# cyclone4.net
KiCad netlist of a schematic drawn in Altium Designer
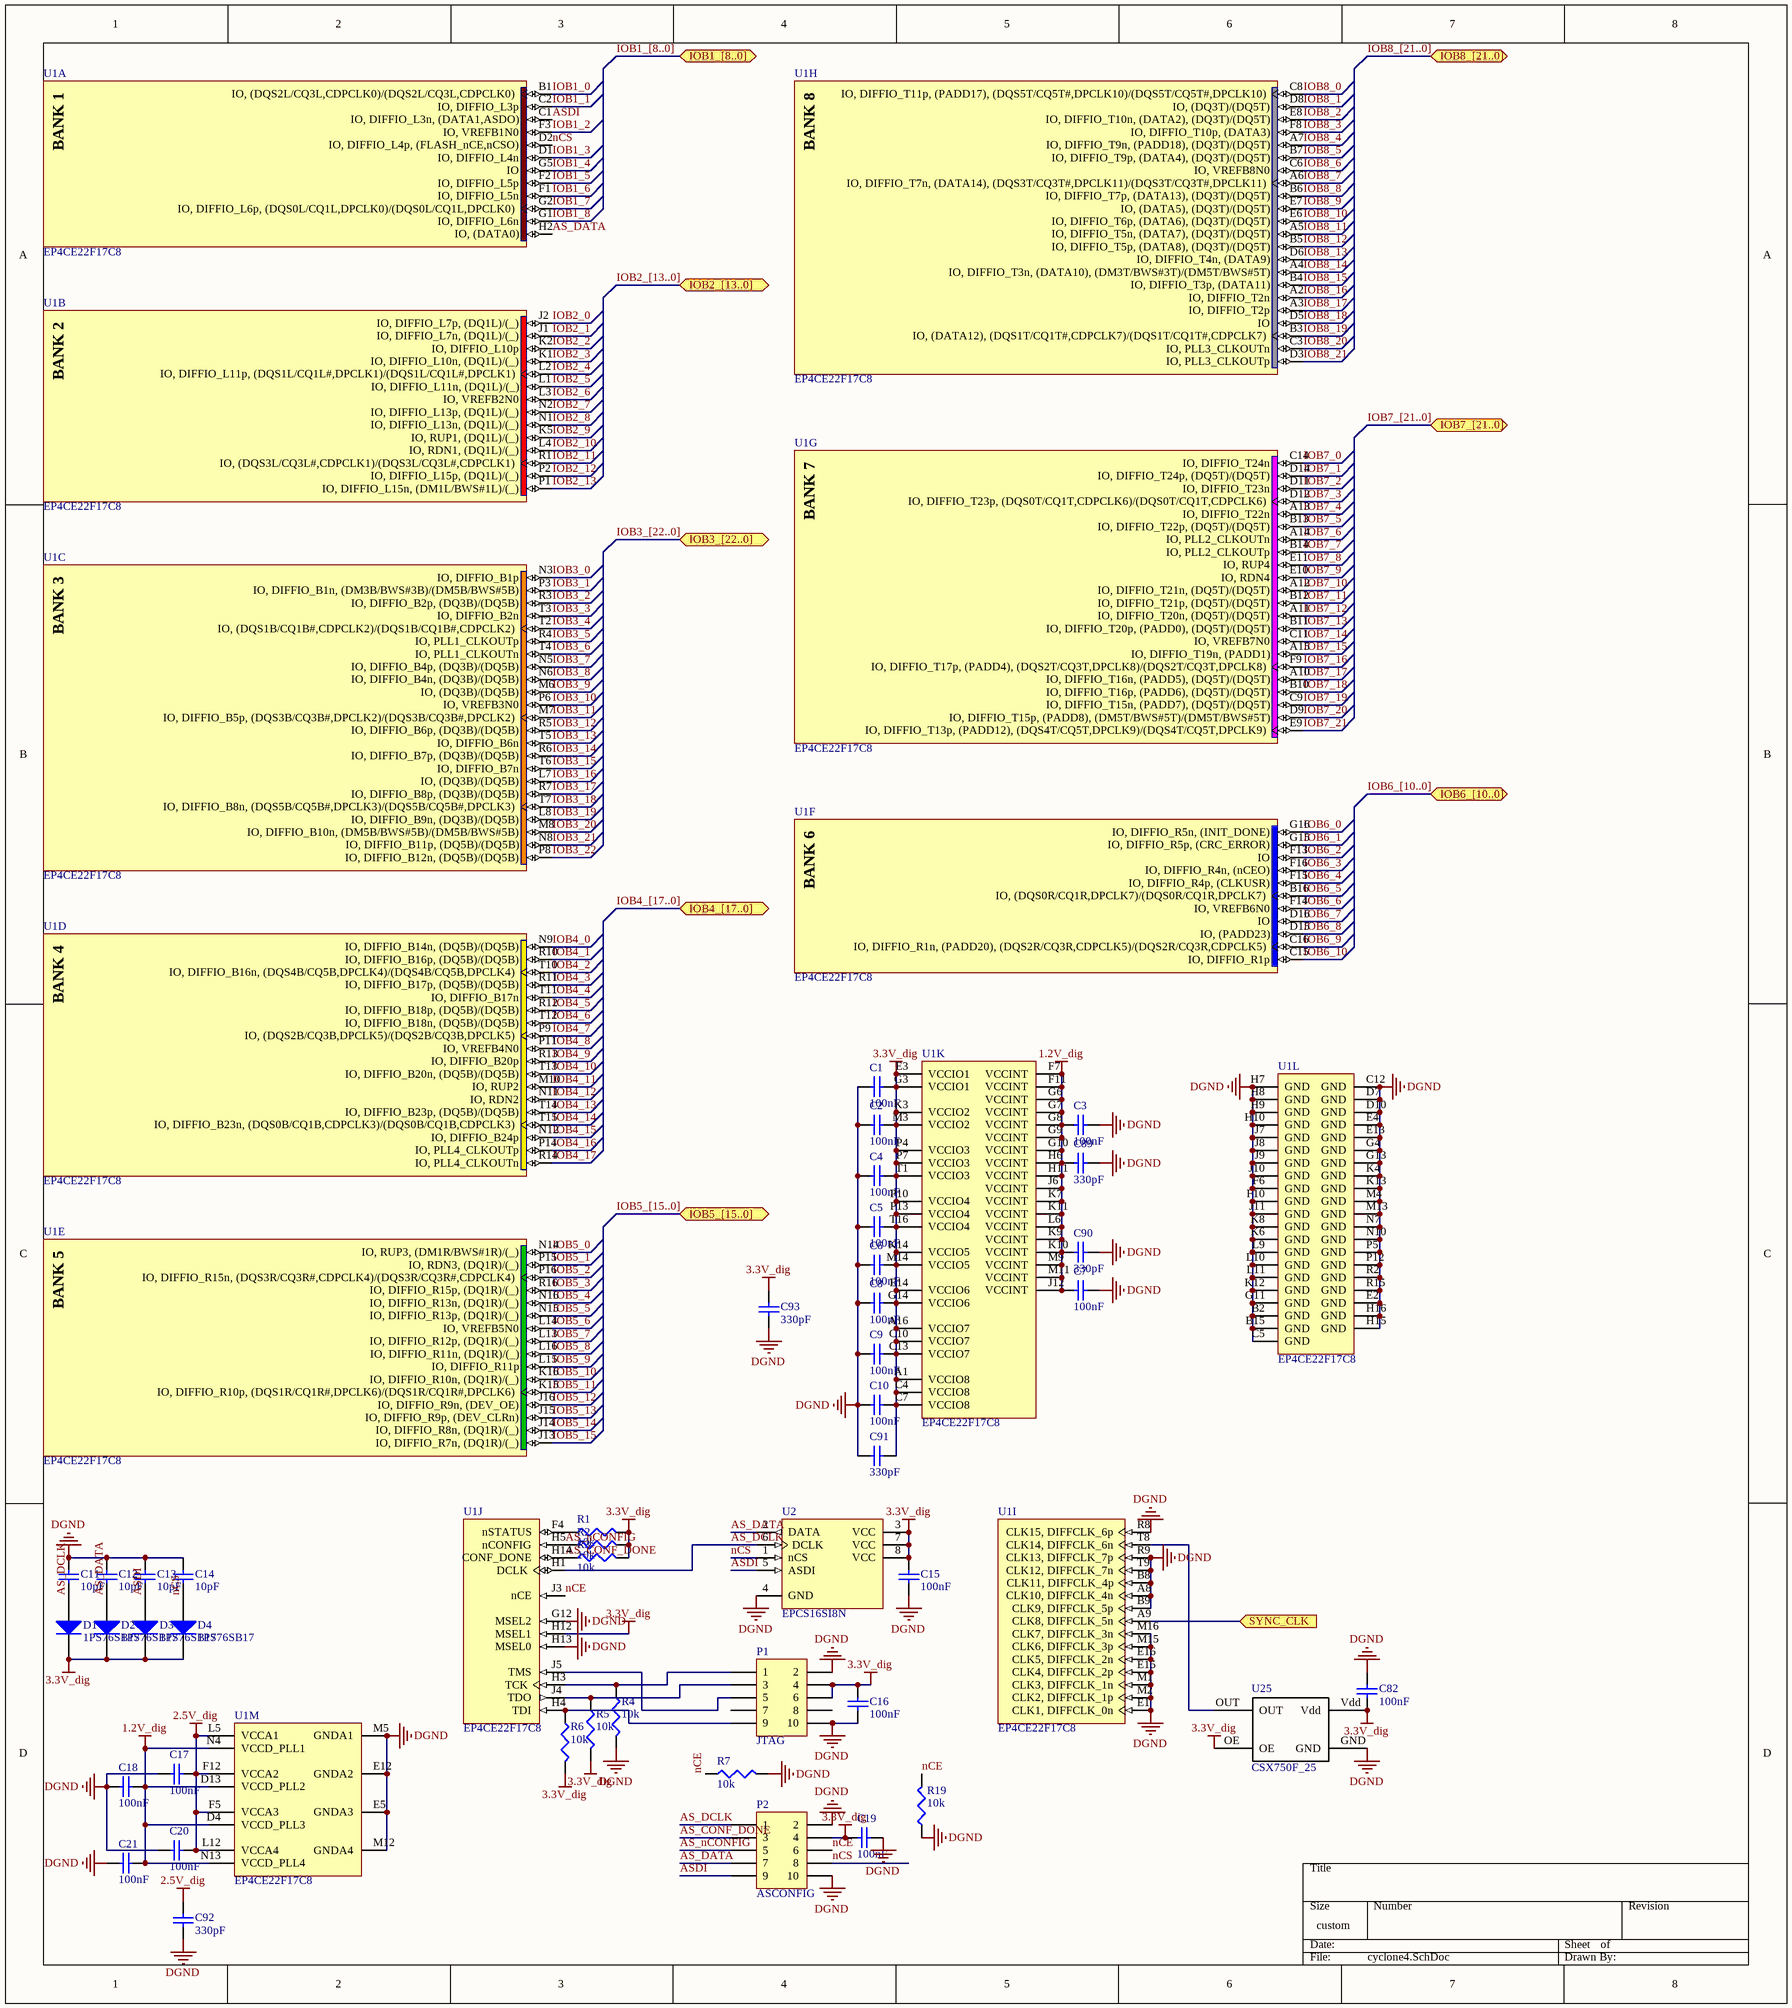
[diagram p0: cyclone4.SchDoc]

(export (version "E")
  (design (tool "Eeschema 10.0.6"))
  (components
    (comp (ref "C1")
      (value "100nF")
      (footprint "CAPC2012L")
      (description "Capacitor (Semiconductor SIM Model)")
      (fields (field (name "Comment") "Cap Semi"))
      (libsource (lib "Miscellaneous Devices") (part "Cap Semi"))
    )
    (comp (ref "C2")
      (value "100nF")
      (footprint "CAPC2012L")
      (description "Capacitor (Semiconductor SIM Model)")
      (fields (field (name "Comment") "Cap Semi"))
      (libsource (lib "Miscellaneous Devices") (part "Cap Semi"))
    )
    (comp (ref "C3")
      (value "100nF")
      (footprint "CAPC2012L")
      (description "Capacitor (Semiconductor SIM Model)")
      (fields (field (name "Comment") "Cap Semi"))
      (libsource (lib "Miscellaneous Devices") (part "Cap Semi"))
    )
    (comp (ref "C4")
      (value "100nF")
      (footprint "CAPC2012L")
      (description "Capacitor (Semiconductor SIM Model)")
      (fields (field (name "Comment") "Cap Semi"))
      (libsource (lib "Miscellaneous Devices") (part "Cap Semi"))
    )
    (comp (ref "C5")
      (value "100nF")
      (footprint "CAPC2012L")
      (description "Capacitor (Semiconductor SIM Model)")
      (fields (field (name "Comment") "Cap Semi"))
      (libsource (lib "Miscellaneous Devices") (part "Cap Semi"))
    )
    (comp (ref "C6")
      (value "100nF")
      (footprint "CAPC2012L")
      (description "Capacitor (Semiconductor SIM Model)")
      (fields (field (name "Comment") "Cap Semi"))
      (libsource (lib "Miscellaneous Devices") (part "Cap Semi"))
    )
    (comp (ref "C7")
      (value "100nF")
      (footprint "CAPC2012L")
      (description "Capacitor (Semiconductor SIM Model)")
      (fields (field (name "Comment") "Cap Semi"))
      (libsource (lib "Miscellaneous Devices") (part "Cap Semi"))
    )
    (comp (ref "C8")
      (value "100nF")
      (footprint "CAPC2012L")
      (description "Capacitor (Semiconductor SIM Model)")
      (fields (field (name "Comment") "Cap Semi"))
      (libsource (lib "Miscellaneous Devices") (part "Cap Semi"))
    )
    (comp (ref "C9")
      (value "100nF")
      (footprint "CAPC2012L")
      (description "Capacitor (Semiconductor SIM Model)")
      (fields (field (name "Comment") "Cap Semi"))
      (libsource (lib "Miscellaneous Devices") (part "Cap Semi"))
    )
    (comp (ref "C10")
      (value "100nF")
      (footprint "CAPC2012L")
      (description "Capacitor (Semiconductor SIM Model)")
      (fields (field (name "Comment") "Cap Semi"))
      (libsource (lib "Miscellaneous Devices") (part "Cap Semi"))
    )
    (comp (ref "C11")
      (value "10pF")
      (footprint "CAPC2012L")
      (description "Capacitor (Semiconductor SIM Model)")
      (fields (field (name "Comment") "Cap Semi"))
      (libsource (lib "Miscellaneous Devices") (part "Cap Semi"))
    )
    (comp (ref "C12")
      (value "10pF")
      (footprint "CAPC2012L")
      (description "Capacitor (Semiconductor SIM Model)")
      (fields (field (name "Comment") "Cap Semi"))
      (libsource (lib "Miscellaneous Devices") (part "Cap Semi"))
    )
    (comp (ref "C13")
      (value "10pF")
      (footprint "CAPC2012L")
      (description "Capacitor (Semiconductor SIM Model)")
      (fields (field (name "Comment") "Cap Semi"))
      (libsource (lib "Miscellaneous Devices") (part "Cap Semi"))
    )
    (comp (ref "C14")
      (value "10pF")
      (footprint "CAPC2012L")
      (description "Capacitor (Semiconductor SIM Model)")
      (fields (field (name "Comment") "Cap Semi"))
      (libsource (lib "Miscellaneous Devices") (part "Cap Semi"))
    )
    (comp (ref "C15")
      (value "100nF")
      (footprint "CAPC2012L")
      (description "Capacitor (Semiconductor SIM Model)")
      (fields (field (name "Comment") "Cap Semi"))
      (libsource (lib "Miscellaneous Devices") (part "Cap Semi"))
    )
    (comp (ref "C16")
      (value "100nF")
      (footprint "CAPC2012L")
      (description "Capacitor (Semiconductor SIM Model)")
      (fields (field (name "Comment") "Cap Semi"))
      (libsource (lib "Miscellaneous Devices") (part "Cap Semi"))
    )
    (comp (ref "C17")
      (value "100nF")
      (footprint "CAPC2012L")
      (description "Capacitor (Semiconductor SIM Model)")
      (fields (field (name "Comment") "Cap Semi"))
      (libsource (lib "Miscellaneous Devices") (part "Cap Semi"))
    )
    (comp (ref "C18")
      (value "100nF")
      (footprint "CAPC2012L")
      (description "Capacitor (Semiconductor SIM Model)")
      (fields (field (name "Comment") "Cap Semi"))
      (libsource (lib "Miscellaneous Devices") (part "Cap Semi"))
    )
    (comp (ref "C19")
      (value "100nF")
      (footprint "CAPC2012L")
      (description "Capacitor (Semiconductor SIM Model)")
      (fields (field (name "Comment") "Cap Semi"))
      (libsource (lib "Miscellaneous Devices") (part "Cap Semi"))
    )
    (comp (ref "C20")
      (value "100nF")
      (footprint "CAPC2012L")
      (description "Capacitor (Semiconductor SIM Model)")
      (fields (field (name "Comment") "Cap Semi"))
      (libsource (lib "Miscellaneous Devices") (part "Cap Semi"))
    )
    (comp (ref "C21")
      (value "100nF")
      (footprint "CAPC2012L")
      (description "Capacitor (Semiconductor SIM Model)")
      (fields (field (name "Comment") "Cap Semi"))
      (libsource (lib "Miscellaneous Devices") (part "Cap Semi"))
    )
    (comp (ref "C82")
      (value "100nF")
      (footprint "CAPC2012L")
      (description "Capacitor (Semiconductor SIM Model)")
      (fields (field (name "Comment") "Cap Semi"))
      (libsource (lib "Miscellaneous Devices") (part "Cap Semi"))
    )
    (comp (ref "C89")
      (value "330pF")
      (footprint "CAPC2012L")
      (description "Capacitor (Semiconductor SIM Model)")
      (fields (field (name "Comment") "Cap Semi"))
      (libsource (lib "Miscellaneous Devices") (part "Cap Semi"))
    )
    (comp (ref "C90")
      (value "330pF")
      (footprint "CAPC2012L")
      (description "Capacitor (Semiconductor SIM Model)")
      (fields (field (name "Comment") "Cap Semi"))
      (libsource (lib "Miscellaneous Devices") (part "Cap Semi"))
    )
    (comp (ref "C91")
      (value "330pF")
      (footprint "CAPC2012L")
      (description "Capacitor (Semiconductor SIM Model)")
      (fields (field (name "Comment") "Cap Semi"))
      (libsource (lib "Miscellaneous Devices") (part "Cap Semi"))
    )
    (comp (ref "C92")
      (value "330pF")
      (footprint "CAPC2012L")
      (description "Capacitor (Semiconductor SIM Model)")
      (fields (field (name "Comment") "Cap Semi"))
      (libsource (lib "Miscellaneous Devices") (part "Cap Semi"))
    )
    (comp (ref "C93")
      (value "330pF")
      (footprint "CAPC2012L")
      (description "Capacitor (Semiconductor SIM Model)")
      (fields (field (name "Comment") "Cap Semi"))
      (libsource (lib "Miscellaneous Devices") (part "Cap Semi"))
    )
    (comp (ref "D1")
      (value "1PS76SB17")
      (footprint "SOD323")
      (description "Default Diode")
      (libsource (lib "Miscellaneous Devices") (part "Diode"))
    )
    (comp (ref "D2")
      (value "1PS76SB17")
      (footprint "SOD323")
      (description "Default Diode")
      (libsource (lib "Miscellaneous Devices") (part "Diode"))
    )
    (comp (ref "D3")
      (value "1PS76SB17")
      (footprint "SOD323")
      (description "Default Diode")
      (libsource (lib "Miscellaneous Devices") (part "Diode"))
    )
    (comp (ref "D4")
      (value "1PS76SB17")
      (footprint "SOD323")
      (description "Default Diode")
      (libsource (lib "Miscellaneous Devices") (part "Diode"))
    )
    (comp (ref "P1")
      (value "JTAG")
      (footprint "HDR2X5")
      (description "Header, 5-Pin, Dual row")
      (libsource (lib "Miscellaneous Connectors") (part "Header 5X2"))
    )
    (comp (ref "P2")
      (value "ASCONFIG")
      (footprint "HDR2X5")
      (description "Header, 5-Pin, Dual row")
      (libsource (lib "Miscellaneous Connectors") (part "Header 5X2"))
    )
    (comp (ref "R1")
      (value "10k")
      (footprint "RESC3216L")
      (description "Resistor")
      (libsource (lib "Miscellaneous Devices") (part "Res3"))
    )
    (comp (ref "R2")
      (value "10k")
      (footprint "RESC3216L")
      (description "Resistor")
      (libsource (lib "Miscellaneous Devices") (part "Res3"))
    )
    (comp (ref "R3")
      (value "10k")
      (footprint "RESC3216L")
      (description "Resistor")
      (libsource (lib "Miscellaneous Devices") (part "Res3"))
    )
    (comp (ref "R4")
      (value "10k")
      (footprint "RESC3216L")
      (description "Resistor")
      (libsource (lib "Miscellaneous Devices") (part "Res3"))
    )
    (comp (ref "R5")
      (value "10k")
      (footprint "RESC3216L")
      (description "Resistor")
      (libsource (lib "Miscellaneous Devices") (part "Res3"))
    )
    (comp (ref "R6")
      (value "10k")
      (footprint "RESC3216L")
      (description "Resistor")
      (libsource (lib "Miscellaneous Devices") (part "Res3"))
    )
    (comp (ref "R7")
      (value "10k")
      (footprint "RESC3216L")
      (description "Resistor")
      (libsource (lib "Miscellaneous Devices") (part "Res3"))
    )
    (comp (ref "R19")
      (value "10k")
      (footprint "RESC3216L")
      (description "Resistor")
      (libsource (lib "Miscellaneous Devices") (part "Res3"))
    )
    (comp (ref "U1")
      (value "EP4CE22F17C8")
      (footprint "FBGA256")
      (libsource (lib "Altera Cyclone IV E") (part "EP4CE22F17C8"))
    )
    (comp (ref "U2")
      (value "EPCS16SI8N")
      (footprint "SOIC8_L")
      (libsource (lib "Altera EPCS Configuration Device") (part "EPCS4SI8N"))
    )
    (comp (ref "U25")
      (value "CSX750F_25")
      (footprint "CSX750F")
      (description "Clock Oscillator")
      (libsource (lib "HH_chips") (part "CSX750F"))
    )
  )
  (nets
    (net (code "1") (name "/ASDI") (class "Default")
      (node (ref "C13") (pin "1") (pinfunction "1_1") (pintype "passive"))
      (node (ref "D3") (pin "1") (pinfunction "A_1") (pintype "passive"))
      (node (ref "P2") (pin "9") (pinfunction "9_9") (pintype "passive"))
      (node (ref "U1") (pin "C1") (pinfunction "IO,_DIFFIO_L3n,_(DATA1,ASDO)_C1") (pintype "bidirectional"))
      (node (ref "U2") (pin "5") (pinfunction "ASDI_5") (pintype "input"))
    )
    (net (code "2") (name "/AS_CONF_DONE") (class "Default")
      (node (ref "P2") (pin "3") (pinfunction "3_3") (pintype "passive"))
      (node (ref "R3") (pin "1") (pinfunction "1_1") (pintype "passive"))
      (node (ref "U1") (pin "H14") (pinfunction "CONF_DONE_H14") (pintype "bidirectional"))
    )
    (net (code "3") (name "/AS_DATA") (class "Default")
      (node (ref "C12") (pin "1") (pinfunction "1_1") (pintype "passive"))
      (node (ref "D2") (pin "1") (pinfunction "A_1") (pintype "passive"))
      (node (ref "P2") (pin "7") (pinfunction "7_7") (pintype "passive"))
      (node (ref "U1") (pin "H2") (pinfunction "IO,_(DATA0)_H2") (pintype "bidirectional"))
      (node (ref "U2") (pin "2") (pinfunction "DATA_2") (pintype "output"))
    )
    (net (code "4") (name "/AS_DCLK") (class "Default")
      (node (ref "C11") (pin "1") (pinfunction "1_1") (pintype "passive"))
      (node (ref "D1") (pin "1") (pinfunction "A_1") (pintype "passive"))
      (node (ref "P2") (pin "1") (pinfunction "1_1") (pintype "passive"))
      (node (ref "U1") (pin "H1") (pinfunction "DCLK_H1") (pintype "bidirectional"))
      (node (ref "U2") (pin "6") (pinfunction "DCLK_6") (pintype "input"))
    )
    (net (code "5") (name "/AS_nCONFIG") (class "Default")
      (node (ref "P2") (pin "5") (pinfunction "5_5") (pintype "passive"))
      (node (ref "R2") (pin "1") (pinfunction "1_1") (pintype "passive"))
      (node (ref "U1") (pin "H5") (pinfunction "nCONFIG_H5") (pintype "input"))
    )
    (net (code "6") (name "/IOB1_0") (class "Default")
      (node (ref "U1") (pin "B1") (pinfunction "IO,_(DQS2L/CQ3L,CDPCLK0)/(DQS2L/CQ3L,CDPCLK0)_B1") (pintype "bidirectional"))
    )
    (net (code "7") (name "/IOB1_1") (class "Default")
      (node (ref "U1") (pin "C2") (pinfunction "IO,_DIFFIO_L3p_C2") (pintype "bidirectional"))
    )
    (net (code "8") (name "/IOB1_2") (class "Default")
      (node (ref "U1") (pin "F3") (pinfunction "IO,_VREFB1N0_F3") (pintype "bidirectional"))
    )
    (net (code "9") (name "/IOB1_3") (class "Default")
      (node (ref "U1") (pin "D1") (pinfunction "IO,_DIFFIO_L4n_D1") (pintype "bidirectional"))
    )
    (net (code "10") (name "/IOB1_4") (class "Default")
      (node (ref "U1") (pin "G5") (pinfunction "IO_G5") (pintype "bidirectional"))
    )
    (net (code "11") (name "/IOB1_5") (class "Default")
      (node (ref "U1") (pin "F2") (pinfunction "IO,_DIFFIO_L5p_F2") (pintype "bidirectional"))
    )
    (net (code "12") (name "/IOB1_6") (class "Default")
      (node (ref "U1") (pin "F1") (pinfunction "IO,_DIFFIO_L5n_F1") (pintype "bidirectional"))
    )
    (net (code "13") (name "/IOB1_7") (class "Default")
      (node (ref "U1") (pin "G2") (pinfunction "IO,_DIFFIO_L6p,_(DQS0L/CQ1L,DPCLK0)/(DQS0L/CQ1L,DPCLK0)_G2") (pintype "bidirectional"))
    )
    (net (code "14") (name "/IOB1_8") (class "Default")
      (node (ref "U1") (pin "G1") (pinfunction "IO,_DIFFIO_L6n_G1") (pintype "bidirectional"))
    )
    (net (code "16") (name "/IOB2_0") (class "Default")
      (node (ref "U1") (pin "J2") (pinfunction "IO,_DIFFIO_L7p,_(DQ1L)/(_)_J2") (pintype "bidirectional"))
    )
    (net (code "17") (name "/IOB2_1") (class "Default")
      (node (ref "U1") (pin "J1") (pinfunction "IO,_DIFFIO_L7n,_(DQ1L)/(_)_J1") (pintype "bidirectional"))
    )
    (net (code "18") (name "/IOB2_2") (class "Default")
      (node (ref "U1") (pin "K2") (pinfunction "IO,_DIFFIO_L10p_K2") (pintype "bidirectional"))
    )
    (net (code "19") (name "/IOB2_3") (class "Default")
      (node (ref "U1") (pin "K1") (pinfunction "IO,_DIFFIO_L10n,_(DQ1L)/(_)_K1") (pintype "bidirectional"))
    )
    (net (code "20") (name "/IOB2_4") (class "Default")
      (node (ref "U1") (pin "L2") (pinfunction "IO,_DIFFIO_L11p,_(DQS1L/CQ1L#,DPCLK1)/(DQS1L/CQ1L#,DPCLK1)_L2") (pintype "bidirectional"))
    )
    (net (code "21") (name "/IOB2_5") (class "Default")
      (node (ref "U1") (pin "L1") (pinfunction "IO,_DIFFIO_L11n,_(DQ1L)/(_)_L1") (pintype "bidirectional"))
    )
    (net (code "22") (name "/IOB2_6") (class "Default")
      (node (ref "U1") (pin "L3") (pinfunction "IO,_VREFB2N0_L3") (pintype "bidirectional"))
    )
    (net (code "23") (name "/IOB2_7") (class "Default")
      (node (ref "U1") (pin "N2") (pinfunction "IO,_DIFFIO_L13p,_(DQ1L)/(_)_N2") (pintype "bidirectional"))
    )
    (net (code "24") (name "/IOB2_8") (class "Default")
      (node (ref "U1") (pin "N1") (pinfunction "IO,_DIFFIO_L13n,_(DQ1L)/(_)_N1") (pintype "bidirectional"))
    )
    (net (code "25") (name "/IOB2_9") (class "Default")
      (node (ref "U1") (pin "K5") (pinfunction "IO,_RUP1,_(DQ1L)/(_)_K5") (pintype "bidirectional"))
    )
    (net (code "26") (name "/IOB2_10") (class "Default")
      (node (ref "U1") (pin "L4") (pinfunction "IO,_RDN1,_(DQ1L)/(_)_L4") (pintype "bidirectional"))
    )
    (net (code "27") (name "/IOB2_11") (class "Default")
      (node (ref "U1") (pin "R1") (pinfunction "IO,_(DQS3L/CQ3L#,CDPCLK1)/(DQS3L/CQ3L#,CDPCLK1)_R1") (pintype "bidirectional"))
    )
    (net (code "28") (name "/IOB2_12") (class "Default")
      (node (ref "U1") (pin "P2") (pinfunction "IO,_DIFFIO_L15p,_(DQ1L)/(_)_P2") (pintype "bidirectional"))
    )
    (net (code "29") (name "/IOB2_13") (class "Default")
      (node (ref "U1") (pin "P1") (pinfunction "IO,_DIFFIO_L15n,_(DM1L/BWS#1L)/(_)_P1") (pintype "bidirectional"))
    )
    (net (code "31") (name "/IOB3_0") (class "Default")
      (node (ref "U1") (pin "N3") (pinfunction "IO,_DIFFIO_B1p_N3") (pintype "bidirectional"))
    )
    (net (code "32") (name "/IOB3_1") (class "Default")
      (node (ref "U1") (pin "P3") (pinfunction "IO,_DIFFIO_B1n,_(DM3B/BWS#3B)/(DM5B/BWS#5B)_P3") (pintype "bidirectional"))
    )
    (net (code "33") (name "/IOB3_2") (class "Default")
      (node (ref "U1") (pin "R3") (pinfunction "IO,_DIFFIO_B2p,_(DQ3B)/(DQ5B)_R3") (pintype "bidirectional"))
    )
    (net (code "34") (name "/IOB3_3") (class "Default")
      (node (ref "U1") (pin "T3") (pinfunction "IO,_DIFFIO_B2n_T3") (pintype "bidirectional"))
    )
    (net (code "35") (name "/IOB3_4") (class "Default")
      (node (ref "U1") (pin "T2") (pinfunction "IO,_(DQS1B/CQ1B#,CDPCLK2)/(DQS1B/CQ1B#,CDPCLK2)_T2") (pintype "bidirectional"))
    )
    (net (code "36") (name "/IOB3_5") (class "Default")
      (node (ref "U1") (pin "R4") (pinfunction "IO,_PLL1_CLKOUTp_R4") (pintype "bidirectional"))
    )
    (net (code "37") (name "/IOB3_6") (class "Default")
      (node (ref "U1") (pin "T4") (pinfunction "IO,_PLL1_CLKOUTn_T4") (pintype "bidirectional"))
    )
    (net (code "38") (name "/IOB3_7") (class "Default")
      (node (ref "U1") (pin "N5") (pinfunction "IO,_DIFFIO_B4p,_(DQ3B)/(DQ5B)_N5") (pintype "bidirectional"))
    )
    (net (code "39") (name "/IOB3_8") (class "Default")
      (node (ref "U1") (pin "N6") (pinfunction "IO,_DIFFIO_B4n,_(DQ3B)/(DQ5B)_N6") (pintype "bidirectional"))
    )
    (net (code "40") (name "/IOB3_9") (class "Default")
      (node (ref "U1") (pin "M6") (pinfunction "IO,_(DQ3B)/(DQ5B)_M6") (pintype "bidirectional"))
    )
    (net (code "41") (name "/IOB3_10") (class "Default")
      (node (ref "U1") (pin "P6") (pinfunction "IO,_VREFB3N0_P6") (pintype "bidirectional"))
    )
    (net (code "42") (name "/IOB3_11") (class "Default")
      (node (ref "U1") (pin "M7") (pinfunction "IO,_DIFFIO_B5p,_(DQS3B/CQ3B#,DPCLK2)/(DQS3B/CQ3B#,DPCLK2)_M7") (pintype "bidirectional"))
    )
    (net (code "43") (name "/IOB3_12") (class "Default")
      (node (ref "U1") (pin "R5") (pinfunction "IO,_DIFFIO_B6p,_(DQ3B)/(DQ5B)_R5") (pintype "bidirectional"))
    )
    (net (code "44") (name "/IOB3_13") (class "Default")
      (node (ref "U1") (pin "T5") (pinfunction "IO,_DIFFIO_B6n_T5") (pintype "bidirectional"))
    )
    (net (code "45") (name "/IOB3_14") (class "Default")
      (node (ref "U1") (pin "R6") (pinfunction "IO,_DIFFIO_B7p,_(DQ3B)/(DQ5B)_R6") (pintype "bidirectional"))
    )
    (net (code "46") (name "/IOB3_15") (class "Default")
      (node (ref "U1") (pin "T6") (pinfunction "IO,_DIFFIO_B7n_T6") (pintype "bidirectional"))
    )
    (net (code "47") (name "/IOB3_16") (class "Default")
      (node (ref "U1") (pin "L7") (pinfunction "IO,_(DQ3B)/(DQ5B)_L7") (pintype "bidirectional"))
    )
    (net (code "48") (name "/IOB3_17") (class "Default")
      (node (ref "U1") (pin "R7") (pinfunction "IO,_DIFFIO_B8p,_(DQ3B)/(DQ5B)_R7") (pintype "bidirectional"))
    )
    (net (code "49") (name "/IOB3_18") (class "Default")
      (node (ref "U1") (pin "T7") (pinfunction "IO,_DIFFIO_B8n,_(DQS5B/CQ5B#,DPCLK3)/(DQS5B/CQ5B#,DPCLK3)_T7") (pintype "bidirectional"))
    )
    (net (code "50") (name "/IOB3_19") (class "Default")
      (node (ref "U1") (pin "L8") (pinfunction "IO,_DIFFIO_B9n,_(DQ3B)/(DQ5B)_L8") (pintype "bidirectional"))
    )
    (net (code "51") (name "/IOB3_20") (class "Default")
      (node (ref "U1") (pin "M8") (pinfunction "IO,_DIFFIO_B10n,_(DM5B/BWS#5B)/(DM5B/BWS#5B)_M8") (pintype "bidirectional"))
    )
    (net (code "52") (name "/IOB3_21") (class "Default")
      (node (ref "U1") (pin "N8") (pinfunction "IO,_DIFFIO_B11p,_(DQ5B)/(DQ5B)_N8") (pintype "bidirectional"))
    )
    (net (code "53") (name "/IOB3_22") (class "Default")
      (node (ref "U1") (pin "P8") (pinfunction "IO,_DIFFIO_B12n,_(DQ5B)/(DQ5B)_P8") (pintype "bidirectional"))
    )
    (net (code "55") (name "/IOB4_0") (class "Default")
      (node (ref "U1") (pin "N9") (pinfunction "IO,_DIFFIO_B14n,_(DQ5B)/(DQ5B)_N9") (pintype "bidirectional"))
    )
    (net (code "56") (name "/IOB4_1") (class "Default")
      (node (ref "U1") (pin "R10") (pinfunction "IO,_DIFFIO_B16p,_(DQ5B)/(DQ5B)_R10") (pintype "bidirectional"))
    )
    (net (code "57") (name "/IOB4_2") (class "Default")
      (node (ref "U1") (pin "T10") (pinfunction "IO,_DIFFIO_B16n,_(DQS4B/CQ5B,DPCLK4)/(DQS4B/CQ5B,DPCLK4)_T10") (pintype "bidirectional"))
    )
    (net (code "58") (name "/IOB4_3") (class "Default")
      (node (ref "U1") (pin "R11") (pinfunction "IO,_DIFFIO_B17p,_(DQ5B)/(DQ5B)_R11") (pintype "bidirectional"))
    )
    (net (code "59") (name "/IOB4_4") (class "Default")
      (node (ref "U1") (pin "T11") (pinfunction "IO,_DIFFIO_B17n_T11") (pintype "bidirectional"))
    )
    (net (code "60") (name "/IOB4_5") (class "Default")
      (node (ref "U1") (pin "R12") (pinfunction "IO,_DIFFIO_B18p,_(DQ5B)/(DQ5B)_R12") (pintype "bidirectional"))
    )
    (net (code "61") (name "/IOB4_6") (class "Default")
      (node (ref "U1") (pin "T12") (pinfunction "IO,_DIFFIO_B18n,_(DQ5B)/(DQ5B)_T12") (pintype "bidirectional"))
    )
    (net (code "62") (name "/IOB4_7") (class "Default")
      (node (ref "U1") (pin "P9") (pinfunction "IO,_(DQS2B/CQ3B,DPCLK5)/(DQS2B/CQ3B,DPCLK5)_P9") (pintype "bidirectional"))
    )
    (net (code "63") (name "/IOB4_8") (class "Default")
      (node (ref "U1") (pin "P11") (pinfunction "IO,_VREFB4N0_P11") (pintype "bidirectional"))
    )
    (net (code "64") (name "/IOB4_9") (class "Default")
      (node (ref "U1") (pin "R13") (pinfunction "IO,_DIFFIO_B20p_R13") (pintype "bidirectional"))
    )
    (net (code "65") (name "/IOB4_10") (class "Default")
      (node (ref "U1") (pin "T13") (pinfunction "IO,_DIFFIO_B20n,_(DQ5B)/(DQ5B)_T13") (pintype "bidirectional"))
    )
    (net (code "66") (name "/IOB4_11") (class "Default")
      (node (ref "U1") (pin "M10") (pinfunction "IO,_RUP2_M10") (pintype "bidirectional"))
    )
    (net (code "67") (name "/IOB4_12") (class "Default")
      (node (ref "U1") (pin "N11") (pinfunction "IO,_RDN2_N11") (pintype "bidirectional"))
    )
    (net (code "68") (name "/IOB4_13") (class "Default")
      (node (ref "U1") (pin "T14") (pinfunction "IO,_DIFFIO_B23p,_(DQ5B)/(DQ5B)_T14") (pintype "bidirectional"))
    )
    (net (code "69") (name "/IOB4_14") (class "Default")
      (node (ref "U1") (pin "T15") (pinfunction "IO,_DIFFIO_B23n,_(DQS0B/CQ1B,CDPCLK3)/(DQS0B/CQ1B,CDPCLK3)_T15") (pintype "bidirectional"))
    )
    (net (code "70") (name "/IOB4_15") (class "Default")
      (node (ref "U1") (pin "N12") (pinfunction "IO,_DIFFIO_B24p_N12") (pintype "bidirectional"))
    )
    (net (code "71") (name "/IOB4_16") (class "Default")
      (node (ref "U1") (pin "P14") (pinfunction "IO,_PLL4_CLKOUTp_P14") (pintype "bidirectional"))
    )
    (net (code "72") (name "/IOB4_17") (class "Default")
      (node (ref "U1") (pin "R14") (pinfunction "IO,_PLL4_CLKOUTn_R14") (pintype "bidirectional"))
    )
    (net (code "74") (name "/IOB5_0") (class "Default")
      (node (ref "U1") (pin "N14") (pinfunction "IO,_RUP3,_(DM1R/BWS#1R)/(_)_N14") (pintype "bidirectional"))
    )
    (net (code "75") (name "/IOB5_1") (class "Default")
      (node (ref "U1") (pin "P15") (pinfunction "IO,_RDN3,_(DQ1R)/(_)_P15") (pintype "bidirectional"))
    )
    (net (code "76") (name "/IOB5_2") (class "Default")
      (node (ref "U1") (pin "P16") (pinfunction "IO,_DIFFIO_R15n,_(DQS3R/CQ3R#,CDPCLK4)/(DQS3R/CQ3R#,CDPCLK4)_P16") (pintype "bidirectional"))
    )
    (net (code "77") (name "/IOB5_3") (class "Default")
      (node (ref "U1") (pin "R16") (pinfunction "IO,_DIFFIO_R15p,_(DQ1R)/(_)_R16") (pintype "bidirectional"))
    )
    (net (code "78") (name "/IOB5_4") (class "Default")
      (node (ref "U1") (pin "N16") (pinfunction "IO,_DIFFIO_R13n,_(DQ1R)/(_)_N16") (pintype "bidirectional"))
    )
    (net (code "79") (name "/IOB5_5") (class "Default")
      (node (ref "U1") (pin "N15") (pinfunction "IO,_DIFFIO_R13p,_(DQ1R)/(_)_N15") (pintype "bidirectional"))
    )
    (net (code "80") (name "/IOB5_6") (class "Default")
      (node (ref "U1") (pin "L14") (pinfunction "IO,_VREFB5N0_L14") (pintype "bidirectional"))
    )
    (net (code "81") (name "/IOB5_7") (class "Default")
      (node (ref "U1") (pin "L13") (pinfunction "IO,_DIFFIO_R12p,_(DQ1R)/(_)_L13") (pintype "bidirectional"))
    )
    (net (code "82") (name "/IOB5_8") (class "Default")
      (node (ref "U1") (pin "L16") (pinfunction "IO,_DIFFIO_R11n,_(DQ1R)/(_)_L16") (pintype "bidirectional"))
    )
    (net (code "83") (name "/IOB5_9") (class "Default")
      (node (ref "U1") (pin "L15") (pinfunction "IO,_DIFFIO_R11p_L15") (pintype "bidirectional"))
    )
    (net (code "84") (name "/IOB5_10") (class "Default")
      (node (ref "U1") (pin "K16") (pinfunction "IO,_DIFFIO_R10n,_(DQ1R)/(_)_K16") (pintype "bidirectional"))
    )
    (net (code "85") (name "/IOB5_11") (class "Default")
      (node (ref "U1") (pin "K15") (pinfunction "IO,_DIFFIO_R10p,_(DQS1R/CQ1R#,DPCLK6)/(DQS1R/CQ1R#,DPCLK6)_K15") (pintype "bidirectional"))
    )
    (net (code "86") (name "/IOB5_12") (class "Default")
      (node (ref "U1") (pin "J16") (pinfunction "IO,_DIFFIO_R9n,_(DEV_OE)_J16") (pintype "bidirectional"))
    )
    (net (code "87") (name "/IOB5_13") (class "Default")
      (node (ref "U1") (pin "J15") (pinfunction "IO,_DIFFIO_R9p,_(DEV_CLRn)_J15") (pintype "bidirectional"))
    )
    (net (code "88") (name "/IOB5_14") (class "Default")
      (node (ref "U1") (pin "J14") (pinfunction "IO,_DIFFIO_R8n,_(DQ1R)/(_)_J14") (pintype "bidirectional"))
    )
    (net (code "89") (name "/IOB5_15") (class "Default")
      (node (ref "U1") (pin "J13") (pinfunction "IO,_DIFFIO_R7n,_(DQ1R)/(_)_J13") (pintype "bidirectional"))
    )
    (net (code "91") (name "/IOB6_0") (class "Default")
      (node (ref "U1") (pin "G16") (pinfunction "IO,_DIFFIO_R5n,_(INIT_DONE)_G16") (pintype "bidirectional"))
    )
    (net (code "92") (name "/IOB6_1") (class "Default")
      (node (ref "U1") (pin "G15") (pinfunction "IO,_DIFFIO_R5p,_(CRC_ERROR)_G15") (pintype "bidirectional"))
    )
    (net (code "93") (name "/IOB6_2") (class "Default")
      (node (ref "U1") (pin "F13") (pinfunction "IO_F13") (pintype "bidirectional"))
    )
    (net (code "94") (name "/IOB6_3") (class "Default")
      (node (ref "U1") (pin "F16") (pinfunction "IO,_DIFFIO_R4n,_(nCEO)_F16") (pintype "bidirectional"))
    )
    (net (code "95") (name "/IOB6_4") (class "Default")
      (node (ref "U1") (pin "F15") (pinfunction "IO,_DIFFIO_R4p,_(CLKUSR)_F15") (pintype "bidirectional"))
    )
    (net (code "96") (name "/IOB6_5") (class "Default")
      (node (ref "U1") (pin "B16") (pinfunction "IO,_(DQS0R/CQ1R,DPCLK7)/(DQS0R/CQ1R,DPCLK7)_B16") (pintype "bidirectional"))
    )
    (net (code "97") (name "/IOB6_6") (class "Default")
      (node (ref "U1") (pin "F14") (pinfunction "IO,_VREFB6N0_F14") (pintype "bidirectional"))
    )
    (net (code "98") (name "/IOB6_7") (class "Default")
      (node (ref "U1") (pin "D16") (pinfunction "IO_D16") (pintype "bidirectional"))
    )
    (net (code "99") (name "/IOB6_8") (class "Default")
      (node (ref "U1") (pin "D15") (pinfunction "IO,_(PADD23)_D15") (pintype "bidirectional"))
    )
    (net (code "100") (name "/IOB6_9") (class "Default")
      (node (ref "U1") (pin "C16") (pinfunction "IO,_DIFFIO_R1n,_(PADD20),_(DQS2R/CQ3R,CDPCLK5)/(DQS2R/CQ3R,CDPCLK5)_C16") (pintype "bidirectional"))
    )
    (net (code "101") (name "/IOB6_10") (class "Default")
      (node (ref "U1") (pin "C15") (pinfunction "IO,_DIFFIO_R1p_C15") (pintype "bidirectional"))
    )
    (net (code "103") (name "/IOB7_0") (class "Default")
      (node (ref "U1") (pin "C14") (pinfunction "IO,_DIFFIO_T24n_C14") (pintype "bidirectional"))
    )
    (net (code "104") (name "/IOB7_1") (class "Default")
      (node (ref "U1") (pin "D14") (pinfunction "IO,_DIFFIO_T24p,_(DQ5T)/(DQ5T)_D14") (pintype "bidirectional"))
    )
    (net (code "105") (name "/IOB7_2") (class "Default")
      (node (ref "U1") (pin "D11") (pinfunction "IO,_DIFFIO_T23n_D11") (pintype "bidirectional"))
    )
    (net (code "106") (name "/IOB7_3") (class "Default")
      (node (ref "U1") (pin "D12") (pinfunction "IO,_DIFFIO_T23p,_(DQS0T/CQ1T,CDPCLK6)/(DQS0T/CQ1T,CDPCLK6)_D12") (pintype "bidirectional"))
    )
    (net (code "107") (name "/IOB7_4") (class "Default")
      (node (ref "U1") (pin "A13") (pinfunction "IO,_DIFFIO_T22n_A13") (pintype "bidirectional"))
    )
    (net (code "108") (name "/IOB7_5") (class "Default")
      (node (ref "U1") (pin "B13") (pinfunction "IO,_DIFFIO_T22p,_(DQ5T)/(DQ5T)_B13") (pintype "bidirectional"))
    )
    (net (code "109") (name "/IOB7_6") (class "Default")
      (node (ref "U1") (pin "A14") (pinfunction "IO,_PLL2_CLKOUTn_A14") (pintype "bidirectional"))
    )
    (net (code "110") (name "/IOB7_7") (class "Default")
      (node (ref "U1") (pin "B14") (pinfunction "IO,_PLL2_CLKOUTp_B14") (pintype "bidirectional"))
    )
    (net (code "111") (name "/IOB7_8") (class "Default")
      (node (ref "U1") (pin "E11") (pinfunction "IO,_RUP4_E11") (pintype "bidirectional"))
    )
    (net (code "112") (name "/IOB7_9") (class "Default")
      (node (ref "U1") (pin "E10") (pinfunction "IO,_RDN4_E10") (pintype "bidirectional"))
    )
    (net (code "113") (name "/IOB7_10") (class "Default")
      (node (ref "U1") (pin "A12") (pinfunction "IO,_DIFFIO_T21n,_(DQ5T)/(DQ5T)_A12") (pintype "bidirectional"))
    )
    (net (code "114") (name "/IOB7_11") (class "Default")
      (node (ref "U1") (pin "B12") (pinfunction "IO,_DIFFIO_T21p,_(DQ5T)/(DQ5T)_B12") (pintype "bidirectional"))
    )
    (net (code "115") (name "/IOB7_12") (class "Default")
      (node (ref "U1") (pin "A11") (pinfunction "IO,_DIFFIO_T20n,_(DQ5T)/(DQ5T)_A11") (pintype "bidirectional"))
    )
    (net (code "116") (name "/IOB7_13") (class "Default")
      (node (ref "U1") (pin "B11") (pinfunction "IO,_DIFFIO_T20p,_(PADD0),_(DQ5T)/(DQ5T)_B11") (pintype "bidirectional"))
    )
    (net (code "117") (name "/IOB7_14") (class "Default")
      (node (ref "U1") (pin "C11") (pinfunction "IO,_VREFB7N0_C11") (pintype "bidirectional"))
    )
    (net (code "118") (name "/IOB7_15") (class "Default")
      (node (ref "U1") (pin "A15") (pinfunction "IO,_DIFFIO_T19n,_(PADD1)_A15") (pintype "bidirectional"))
    )
    (net (code "119") (name "/IOB7_16") (class "Default")
      (node (ref "U1") (pin "F9") (pinfunction "IO,_DIFFIO_T17p,_(PADD4),_(DQS2T/CQ3T,DPCLK8)/(DQS2T/CQ3T,DPCLK8)_F9") (pintype "bidirectional"))
    )
    (net (code "120") (name "/IOB7_17") (class "Default")
      (node (ref "U1") (pin "A10") (pinfunction "IO,_DIFFIO_T16n,_(PADD5),_(DQ5T)/(DQ5T)_A10") (pintype "bidirectional"))
    )
    (net (code "121") (name "/IOB7_18") (class "Default")
      (node (ref "U1") (pin "B10") (pinfunction "IO,_DIFFIO_T16p,_(PADD6),_(DQ5T)/(DQ5T)_B10") (pintype "bidirectional"))
    )
    (net (code "122") (name "/IOB7_19") (class "Default")
      (node (ref "U1") (pin "C9") (pinfunction "IO,_DIFFIO_T15n,_(PADD7),_(DQ5T)/(DQ5T)_C9") (pintype "bidirectional"))
    )
    (net (code "123") (name "/IOB7_20") (class "Default")
      (node (ref "U1") (pin "D9") (pinfunction "IO,_DIFFIO_T15p,_(PADD8),_(DM5T/BWS#5T)/(DM5T/BWS#5T)_D9") (pintype "bidirectional"))
    )
    (net (code "124") (name "/IOB7_21") (class "Default")
      (node (ref "U1") (pin "E9") (pinfunction "IO,_DIFFIO_T13p,_(PADD12),_(DQS4T/CQ5T,DPCLK9)/(DQS4T/CQ5T,DPCLK9)_E9") (pintype "bidirectional"))
    )
    (net (code "126") (name "/IOB8_0") (class "Default")
      (node (ref "U1") (pin "C8") (pinfunction "IO,_DIFFIO_T11p,_(PADD17),_(DQS5T/CQ5T#,DPCLK10)/(DQS5T/CQ5T#,DPCLK10)_C8") (pintype "bidirectional"))
    )
    (net (code "127") (name "/IOB8_1") (class "Default")
      (node (ref "U1") (pin "D8") (pinfunction "IO,_(DQ3T)/(DQ5T)_D8") (pintype "bidirectional"))
    )
    (net (code "128") (name "/IOB8_2") (class "Default")
      (node (ref "U1") (pin "E8") (pinfunction "IO,_DIFFIO_T10n,_(DATA2),_(DQ3T)/(DQ5T)_E8") (pintype "bidirectional"))
    )
    (net (code "129") (name "/IOB8_3") (class "Default")
      (node (ref "U1") (pin "F8") (pinfunction "IO,_DIFFIO_T10p,_(DATA3)_F8") (pintype "bidirectional"))
    )
    (net (code "130") (name "/IOB8_4") (class "Default")
      (node (ref "U1") (pin "A7") (pinfunction "IO,_DIFFIO_T9n,_(PADD18),_(DQ3T)/(DQ5T)_A7") (pintype "bidirectional"))
    )
    (net (code "131") (name "/IOB8_5") (class "Default")
      (node (ref "U1") (pin "B7") (pinfunction "IO,_DIFFIO_T9p,_(DATA4),_(DQ3T)/(DQ5T)_B7") (pintype "bidirectional"))
    )
    (net (code "132") (name "/IOB8_6") (class "Default")
      (node (ref "U1") (pin "C6") (pinfunction "IO,_VREFB8N0_C6") (pintype "bidirectional"))
    )
    (net (code "133") (name "/IOB8_7") (class "Default")
      (node (ref "U1") (pin "A6") (pinfunction "IO,_DIFFIO_T7n,_(DATA14),_(DQS3T/CQ3T#,DPCLK11)/(DQS3T/CQ3T#,DPCLK11)_A6") (pintype "bidirectional"))
    )
    (net (code "134") (name "/IOB8_8") (class "Default")
      (node (ref "U1") (pin "B6") (pinfunction "IO,_DIFFIO_T7p,_(DATA13),_(DQ3T)/(DQ5T)_B6") (pintype "bidirectional"))
    )
    (net (code "135") (name "/IOB8_9") (class "Default")
      (node (ref "U1") (pin "E7") (pinfunction "IO,_(DATA5),_(DQ3T)/(DQ5T)_E7") (pintype "bidirectional"))
    )
    (net (code "136") (name "/IOB8_10") (class "Default")
      (node (ref "U1") (pin "E6") (pinfunction "IO,_DIFFIO_T6p,_(DATA6),_(DQ3T)/(DQ5T)_E6") (pintype "bidirectional"))
    )
    (net (code "137") (name "/IOB8_11") (class "Default")
      (node (ref "U1") (pin "A5") (pinfunction "IO,_DIFFIO_T5n,_(DATA7),_(DQ3T)/(DQ5T)_A5") (pintype "bidirectional"))
    )
    (net (code "138") (name "/IOB8_12") (class "Default")
      (node (ref "U1") (pin "B5") (pinfunction "IO,_DIFFIO_T5p,_(DATA8),_(DQ3T)/(DQ5T)_B5") (pintype "bidirectional"))
    )
    (net (code "139") (name "/IOB8_13") (class "Default")
      (node (ref "U1") (pin "D6") (pinfunction "IO,_DIFFIO_T4n,_(DATA9)_D6") (pintype "bidirectional"))
    )
    (net (code "140") (name "/IOB8_14") (class "Default")
      (node (ref "U1") (pin "A4") (pinfunction "IO,_DIFFIO_T3n,_(DATA10),_(DM3T/BWS#3T)/(DM5T/BWS#5T)_A4") (pintype "bidirectional"))
    )
    (net (code "141") (name "/IOB8_15") (class "Default")
      (node (ref "U1") (pin "B4") (pinfunction "IO,_DIFFIO_T3p,_(DATA11)_B4") (pintype "bidirectional"))
    )
    (net (code "142") (name "/IOB8_16") (class "Default")
      (node (ref "U1") (pin "A2") (pinfunction "IO,_DIFFIO_T2n_A2") (pintype "bidirectional"))
    )
    (net (code "143") (name "/IOB8_17") (class "Default")
      (node (ref "U1") (pin "A3") (pinfunction "IO,_DIFFIO_T2p_A3") (pintype "bidirectional"))
    )
    (net (code "144") (name "/IOB8_18") (class "Default")
      (node (ref "U1") (pin "D5") (pinfunction "IO_D5") (pintype "bidirectional"))
    )
    (net (code "145") (name "/IOB8_19") (class "Default")
      (node (ref "U1") (pin "B3") (pinfunction "IO,_(DATA12),_(DQS1T/CQ1T#,CDPCLK7)/(DQS1T/CQ1T#,CDPCLK7)_B3") (pintype "bidirectional"))
    )
    (net (code "146") (name "/IOB8_20") (class "Default")
      (node (ref "U1") (pin "C3") (pinfunction "IO,_PLL3_CLKOUTn_C3") (pintype "bidirectional"))
    )
    (net (code "147") (name "/IOB8_21") (class "Default")
      (node (ref "U1") (pin "D3") (pinfunction "IO,_PLL3_CLKOUTp_D3") (pintype "bidirectional"))
    )
    (net (code "149") (name "/SYNC_CLK") (class "Default")
      (node (ref "U1") (pin "A9") (pinfunction "CLK8,_DIFFCLK_5n_A9") (pintype "input"))
    )
    (net (code "150") (name "/nCE") (class "Default")
      (node (ref "P2") (pin "6") (pinfunction "6_6") (pintype "passive"))
      (node (ref "R19") (pin "2") (pinfunction "2_2") (pintype "passive"))
      (node (ref "R7") (pin "1") (pinfunction "1_1") (pintype "passive"))
      (node (ref "U1") (pin "J3") (pinfunction "nCE_J3") (pintype "input"))
    )
    (net (code "151") (name "/nCS") (class "Default")
      (node (ref "C14") (pin "1") (pinfunction "1_1") (pintype "passive"))
      (node (ref "D4") (pin "1") (pinfunction "A_1") (pintype "passive"))
      (node (ref "P2") (pin "8") (pinfunction "8_8") (pintype "passive"))
      (node (ref "U1") (pin "D2") (pinfunction "IO,_DIFFIO_L4p,_(FLASH_nCE,nCSO)_D2") (pintype "bidirectional"))
      (node (ref "U2") (pin "1") (pinfunction "nCS_1") (pintype "input"))
    )
    (net (code "152") (name "1.2V_dig") (class "Default")
      (node (ref "C18") (pin "2") (pinfunction "2_2") (pintype "passive"))
      (node (ref "C21") (pin "2") (pinfunction "2_2") (pintype "passive"))
      (node (ref "C3") (pin "1") (pinfunction "1_1") (pintype "passive"))
      (node (ref "C7") (pin "1") (pinfunction "1_1") (pintype "passive"))
      (node (ref "C89") (pin "1") (pinfunction "1_1") (pintype "passive"))
      (node (ref "C90") (pin "1") (pinfunction "1_1") (pintype "passive"))
      (node (ref "U1") (pin "D13") (pinfunction "VCCD_PLL2_D13") (pintype "power_in"))
      (node (ref "U1") (pin "D4") (pinfunction "VCCD_PLL3_D4") (pintype "power_in"))
      (node (ref "U1") (pin "F11") (pinfunction "VCCINT_F11") (pintype "power_in"))
      (node (ref "U1") (pin "F7") (pinfunction "VCCINT_F7") (pintype "power_in"))
      (node (ref "U1") (pin "G10") (pinfunction "VCCINT_G10") (pintype "power_in"))
      (node (ref "U1") (pin "G6") (pinfunction "VCCINT_G6") (pintype "power_in"))
      (node (ref "U1") (pin "G7") (pinfunction "VCCINT_G7") (pintype "power_in"))
      (node (ref "U1") (pin "G8") (pinfunction "VCCINT_G8") (pintype "power_in"))
      (node (ref "U1") (pin "G9") (pinfunction "VCCINT_G9") (pintype "power_in"))
      (node (ref "U1") (pin "H11") (pinfunction "VCCINT_H11") (pintype "power_in"))
      (node (ref "U1") (pin "H6") (pinfunction "VCCINT_H6") (pintype "power_in"))
      (node (ref "U1") (pin "J12") (pinfunction "VCCINT_J12") (pintype "power_in"))
      (node (ref "U1") (pin "J6") (pinfunction "VCCINT_J6") (pintype "power_in"))
      (node (ref "U1") (pin "K10") (pinfunction "VCCINT_K10") (pintype "power_in"))
      (node (ref "U1") (pin "K11") (pinfunction "VCCINT_K11") (pintype "power_in"))
      (node (ref "U1") (pin "K7") (pinfunction "VCCINT_K7") (pintype "power_in"))
      (node (ref "U1") (pin "K9") (pinfunction "VCCINT_K9") (pintype "power_in"))
      (node (ref "U1") (pin "L6") (pinfunction "VCCINT_L6") (pintype "power_in"))
      (node (ref "U1") (pin "M11") (pinfunction "VCCINT_M11") (pintype "power_in"))
      (node (ref "U1") (pin "M9") (pinfunction "VCCINT_M9") (pintype "power_in"))
      (node (ref "U1") (pin "N13") (pinfunction "VCCD_PLL4_N13") (pintype "power_in"))
      (node (ref "U1") (pin "N4") (pinfunction "VCCD_PLL1_N4") (pintype "power_in"))
    )
    (net (code "153") (name "2.5V_dig") (class "Default")
      (node (ref "C17") (pin "2") (pinfunction "2_2") (pintype "passive"))
      (node (ref "C20") (pin "1") (pinfunction "1_1") (pintype "passive"))
      (node (ref "C92") (pin "2") (pinfunction "2_2") (pintype "passive"))
      (node (ref "U1") (pin "F12") (pinfunction "VCCA2_F12") (pintype "power_in"))
      (node (ref "U1") (pin "F5") (pinfunction "VCCA3_F5") (pintype "power_in"))
      (node (ref "U1") (pin "L12") (pinfunction "VCCA4_L12") (pintype "power_in"))
      (node (ref "U1") (pin "L5") (pinfunction "VCCA1_L5") (pintype "power_in"))
    )
    (net (code "154") (name "3.3V_dig") (class "Default")
      (node (ref "C1") (pin "2") (pinfunction "2_2") (pintype "passive"))
      (node (ref "C10") (pin "2") (pinfunction "2_2") (pintype "passive"))
      (node (ref "C15") (pin "1") (pinfunction "1_1") (pintype "passive"))
      (node (ref "C16") (pin "1") (pinfunction "1_1") (pintype "passive"))
      (node (ref "C19") (pin "1") (pinfunction "1_1") (pintype "passive"))
      (node (ref "C2") (pin "2") (pinfunction "2_2") (pintype "passive"))
      (node (ref "C4") (pin "2") (pinfunction "2_2") (pintype "passive"))
      (node (ref "C5") (pin "2") (pinfunction "2_2") (pintype "passive"))
      (node (ref "C6") (pin "2") (pinfunction "2_2") (pintype "passive"))
      (node (ref "C8") (pin "2") (pinfunction "2_2") (pintype "passive"))
      (node (ref "C82") (pin "2") (pinfunction "2_2") (pintype "passive"))
      (node (ref "C9") (pin "2") (pinfunction "2_2") (pintype "passive"))
      (node (ref "C91") (pin "2") (pinfunction "2_2") (pintype "passive"))
      (node (ref "C93") (pin "2") (pinfunction "2_2") (pintype "passive"))
      (node (ref "D1") (pin "2") (pinfunction "K_2") (pintype "passive"))
      (node (ref "D2") (pin "2") (pinfunction "K_2") (pintype "passive"))
      (node (ref "D3") (pin "2") (pinfunction "K_2") (pintype "passive"))
      (node (ref "D4") (pin "2") (pinfunction "K_2") (pintype "passive"))
      (node (ref "P1") (pin "4") (pinfunction "4_4") (pintype "passive"))
      (node (ref "P1") (pin "6") (pinfunction "6_6") (pintype "passive"))
      (node (ref "P2") (pin "4") (pinfunction "4_4") (pintype "passive"))
      (node (ref "R1") (pin "2") (pinfunction "2_2") (pintype "passive"))
      (node (ref "R2") (pin "2") (pinfunction "2_2") (pintype "passive"))
      (node (ref "R3") (pin "2") (pinfunction "2_2") (pintype "passive"))
      (node (ref "R5") (pin "2") (pinfunction "2_2") (pintype "passive"))
      (node (ref "R6") (pin "2") (pinfunction "2_2") (pintype "passive"))
      (node (ref "U1") (pin "A1") (pinfunction "VCCIO8_A1") (pintype "power_in"))
      (node (ref "U1") (pin "A16") (pinfunction "VCCIO7_A16") (pintype "power_in"))
      (node (ref "U1") (pin "C10") (pinfunction "VCCIO7_C10") (pintype "power_in"))
      (node (ref "U1") (pin "C13") (pinfunction "VCCIO7_C13") (pintype "power_in"))
      (node (ref "U1") (pin "C4") (pinfunction "VCCIO8_C4") (pintype "power_in"))
      (node (ref "U1") (pin "C7") (pinfunction "VCCIO8_C7") (pintype "power_in"))
      (node (ref "U1") (pin "E14") (pinfunction "VCCIO6_E14") (pintype "power_in"))
      (node (ref "U1") (pin "E3") (pinfunction "VCCIO1_E3") (pintype "power_in"))
      (node (ref "U1") (pin "G14") (pinfunction "VCCIO6_G14") (pintype "power_in"))
      (node (ref "U1") (pin "G3") (pinfunction "VCCIO1_G3") (pintype "power_in"))
      (node (ref "U1") (pin "H12") (pinfunction "MSEL1_H12") (pintype "input"))
      (node (ref "U1") (pin "K14") (pinfunction "VCCIO5_K14") (pintype "power_in"))
      (node (ref "U1") (pin "K3") (pinfunction "VCCIO2_K3") (pintype "power_in"))
      (node (ref "U1") (pin "M14") (pinfunction "VCCIO5_M14") (pintype "power_in"))
      (node (ref "U1") (pin "M3") (pinfunction "VCCIO2_M3") (pintype "power_in"))
      (node (ref "U1") (pin "P10") (pinfunction "VCCIO4_P10") (pintype "power_in"))
      (node (ref "U1") (pin "P13") (pinfunction "VCCIO4_P13") (pintype "power_in"))
      (node (ref "U1") (pin "P4") (pinfunction "VCCIO3_P4") (pintype "power_in"))
      (node (ref "U1") (pin "P7") (pinfunction "VCCIO3_P7") (pintype "power_in"))
      (node (ref "U1") (pin "T1") (pinfunction "VCCIO3_T1") (pintype "power_in"))
      (node (ref "U1") (pin "T16") (pinfunction "VCCIO4_T16") (pintype "power_in"))
      (node (ref "U2") (pin "3") (pinfunction "VCC_3") (pintype "power_in"))
      (node (ref "U2") (pin "7") (pinfunction "VCC_7") (pintype "power_in"))
      (node (ref "U2") (pin "8") (pinfunction "VCC_8") (pintype "power_in"))
      (node (ref "U25") (pin "OE") (pinfunction "OE_OE") (pintype "passive"))
      (node (ref "U25") (pin "Vdd") (pinfunction "Vdd_Vdd") (pintype "passive"))
    )
    (net (code "155") (name "DGND") (class "Default")
      (node (ref "C1") (pin "1") (pinfunction "1_1") (pintype "passive"))
      (node (ref "C10") (pin "1") (pinfunction "1_1") (pintype "passive"))
      (node (ref "C11") (pin "2") (pinfunction "2_2") (pintype "passive"))
      (node (ref "C12") (pin "2") (pinfunction "2_2") (pintype "passive"))
      (node (ref "C13") (pin "2") (pinfunction "2_2") (pintype "passive"))
      (node (ref "C14") (pin "2") (pinfunction "2_2") (pintype "passive"))
      (node (ref "C15") (pin "2") (pinfunction "2_2") (pintype "passive"))
      (node (ref "C16") (pin "2") (pinfunction "2_2") (pintype "passive"))
      (node (ref "C17") (pin "1") (pinfunction "1_1") (pintype "passive"))
      (node (ref "C18") (pin "1") (pinfunction "1_1") (pintype "passive"))
      (node (ref "C19") (pin "2") (pinfunction "2_2") (pintype "passive"))
      (node (ref "C2") (pin "1") (pinfunction "1_1") (pintype "passive"))
      (node (ref "C20") (pin "2") (pinfunction "2_2") (pintype "passive"))
      (node (ref "C21") (pin "1") (pinfunction "1_1") (pintype "passive"))
      (node (ref "C3") (pin "2") (pinfunction "2_2") (pintype "passive"))
      (node (ref "C4") (pin "1") (pinfunction "1_1") (pintype "passive"))
      (node (ref "C5") (pin "1") (pinfunction "1_1") (pintype "passive"))
      (node (ref "C6") (pin "1") (pinfunction "1_1") (pintype "passive"))
      (node (ref "C7") (pin "2") (pinfunction "2_2") (pintype "passive"))
      (node (ref "C8") (pin "1") (pinfunction "1_1") (pintype "passive"))
      (node (ref "C82") (pin "1") (pinfunction "1_1") (pintype "passive"))
      (node (ref "C89") (pin "2") (pinfunction "2_2") (pintype "passive"))
      (node (ref "C9") (pin "1") (pinfunction "1_1") (pintype "passive"))
      (node (ref "C90") (pin "2") (pinfunction "2_2") (pintype "passive"))
      (node (ref "C91") (pin "1") (pinfunction "1_1") (pintype "passive"))
      (node (ref "C92") (pin "1") (pinfunction "1_1") (pintype "passive"))
      (node (ref "C93") (pin "1") (pinfunction "1_1") (pintype "passive"))
      (node (ref "P1") (pin "10") (pinfunction "10_10") (pintype "passive"))
      (node (ref "P1") (pin "2") (pinfunction "2_2") (pintype "passive"))
      (node (ref "P2") (pin "10") (pinfunction "10_10") (pintype "passive"))
      (node (ref "P2") (pin "2") (pinfunction "2_2") (pintype "passive"))
      (node (ref "R19") (pin "1") (pinfunction "1_1") (pintype "passive"))
      (node (ref "R4") (pin "2") (pinfunction "2_2") (pintype "passive"))
      (node (ref "R7") (pin "2") (pinfunction "2_2") (pintype "passive"))
      (node (ref "U1") (pin "A8") (pinfunction "CLK10,_DIFFCLK_4n_A8") (pintype "input"))
      (node (ref "U1") (pin "B15") (pinfunction "GND_B15") (pintype "power_in"))
      (node (ref "U1") (pin "B2") (pinfunction "GND_B2") (pintype "power_in"))
      (node (ref "U1") (pin "B8") (pinfunction "CLK11,_DIFFCLK_4p_B8") (pintype "input"))
      (node (ref "U1") (pin "B9") (pinfunction "CLK9,_DIFFCLK_5p_B9") (pintype "input"))
      (node (ref "U1") (pin "C12") (pinfunction "GND_C12") (pintype "power_in"))
      (node (ref "U1") (pin "C5") (pinfunction "GND_C5") (pintype "power_in"))
      (node (ref "U1") (pin "D10") (pinfunction "GND_D10") (pintype "power_in"))
      (node (ref "U1") (pin "D7") (pinfunction "GND_D7") (pintype "power_in"))
      (node (ref "U1") (pin "E1") (pinfunction "CLK1,_DIFFCLK_0n_E1") (pintype "input"))
      (node (ref "U1") (pin "E12") (pinfunction "GNDA2_E12") (pintype "power_in"))
      (node (ref "U1") (pin "E13") (pinfunction "GND_E13") (pintype "power_in"))
      (node (ref "U1") (pin "E15") (pinfunction "CLK4,_DIFFCLK_2p_E15") (pintype "input"))
      (node (ref "U1") (pin "E16") (pinfunction "CLK5,_DIFFCLK_2n_E16") (pintype "input"))
      (node (ref "U1") (pin "E2") (pinfunction "GND_E2") (pintype "power_in"))
      (node (ref "U1") (pin "E4") (pinfunction "GND_E4") (pintype "power_in"))
      (node (ref "U1") (pin "E5") (pinfunction "GNDA3_E5") (pintype "power_in"))
      (node (ref "U1") (pin "F10") (pinfunction "GND_F10") (pintype "power_in"))
      (node (ref "U1") (pin "F6") (pinfunction "GND_F6") (pintype "power_in"))
      (node (ref "U1") (pin "G11") (pinfunction "GND_G11") (pintype "power_in"))
      (node (ref "U1") (pin "G12") (pinfunction "MSEL2_G12") (pintype "input"))
      (node (ref "U1") (pin "G13") (pinfunction "GND_G13") (pintype "power_in"))
      (node (ref "U1") (pin "G4") (pinfunction "GND_G4") (pintype "power_in"))
      (node (ref "U1") (pin "H10") (pinfunction "GND_H10") (pintype "power_in"))
      (node (ref "U1") (pin "H13") (pinfunction "MSEL0_H13") (pintype "input"))
      (node (ref "U1") (pin "H15") (pinfunction "GND_H15") (pintype "power_in"))
      (node (ref "U1") (pin "H16") (pinfunction "GND_H16") (pintype "power_in"))
      (node (ref "U1") (pin "H7") (pinfunction "GND_H7") (pintype "power_in"))
      (node (ref "U1") (pin "H8") (pinfunction "GND_H8") (pintype "power_in"))
      (node (ref "U1") (pin "H9") (pinfunction "GND_H9") (pintype "power_in"))
      (node (ref "U1") (pin "J10") (pinfunction "GND_J10") (pintype "power_in"))
      (node (ref "U1") (pin "J11") (pinfunction "GND_J11") (pintype "power_in"))
      (node (ref "U1") (pin "J7") (pinfunction "GND_J7") (pintype "power_in"))
      (node (ref "U1") (pin "J8") (pinfunction "GND_J8") (pintype "power_in"))
      (node (ref "U1") (pin "J9") (pinfunction "GND_J9") (pintype "power_in"))
      (node (ref "U1") (pin "K12") (pinfunction "GND_K12") (pintype "power_in"))
      (node (ref "U1") (pin "K13") (pinfunction "GND_K13") (pintype "power_in"))
      (node (ref "U1") (pin "K4") (pinfunction "GND_K4") (pintype "power_in"))
      (node (ref "U1") (pin "K6") (pinfunction "GND_K6") (pintype "power_in"))
      (node (ref "U1") (pin "K8") (pinfunction "GND_K8") (pintype "power_in"))
      (node (ref "U1") (pin "L10") (pinfunction "GND_L10") (pintype "power_in"))
      (node (ref "U1") (pin "L11") (pinfunction "GND_L11") (pintype "power_in"))
      (node (ref "U1") (pin "L9") (pinfunction "GND_L9") (pintype "power_in"))
      (node (ref "U1") (pin "M1") (pinfunction "CLK3,_DIFFCLK_1n_M1") (pintype "input"))
      (node (ref "U1") (pin "M12") (pinfunction "GNDA4_M12") (pintype "power_in"))
      (node (ref "U1") (pin "M13") (pinfunction "GND_M13") (pintype "power_in"))
      (node (ref "U1") (pin "M15") (pinfunction "CLK6,_DIFFCLK_3p_M15") (pintype "input"))
      (node (ref "U1") (pin "M16") (pinfunction "CLK7,_DIFFCLK_3n_M16") (pintype "input"))
      (node (ref "U1") (pin "M2") (pinfunction "CLK2,_DIFFCLK_1p_M2") (pintype "input"))
      (node (ref "U1") (pin "M4") (pinfunction "GND_M4") (pintype "power_in"))
      (node (ref "U1") (pin "M5") (pinfunction "GNDA1_M5") (pintype "power_in"))
      (node (ref "U1") (pin "N10") (pinfunction "GND_N10") (pintype "power_in"))
      (node (ref "U1") (pin "N7") (pinfunction "GND_N7") (pintype "power_in"))
      (node (ref "U1") (pin "P12") (pinfunction "GND_P12") (pintype "power_in"))
      (node (ref "U1") (pin "P5") (pinfunction "GND_P5") (pintype "power_in"))
      (node (ref "U1") (pin "R15") (pinfunction "GND_R15") (pintype "power_in"))
      (node (ref "U1") (pin "R2") (pinfunction "GND_R2") (pintype "power_in"))
      (node (ref "U1") (pin "R8") (pinfunction "CLK15,_DIFFCLK_6p_R8") (pintype "input"))
      (node (ref "U1") (pin "R9") (pinfunction "CLK13,_DIFFCLK_7p_R9") (pintype "input"))
      (node (ref "U1") (pin "T9") (pinfunction "CLK12,_DIFFCLK_7n_T9") (pintype "input"))
      (node (ref "U2") (pin "4") (pinfunction "GND_4") (pintype "power_in"))
      (node (ref "U25") (pin "GND") (pinfunction "GND_GND") (pintype "passive"))
    )
    (net (code "156") (name "Net-(U1I-CLK14,_DIFFCLK_6n)") (class "Default")
      (node (ref "U1") (pin "T8") (pinfunction "CLK14,_DIFFCLK_6n_T8") (pintype "input"))
      (node (ref "U25") (pin "OUT") (pinfunction "OUT_OUT") (pintype "passive"))
    )
    (net (code "157") (name "Net-(U1J-TCK)") (class "Default")
      (node (ref "P1") (pin "1") (pinfunction "1_1") (pintype "passive"))
      (node (ref "R4") (pin "1") (pinfunction "1_1") (pintype "passive"))
      (node (ref "U1") (pin "H3") (pinfunction "TCK_H3") (pintype "input"))
    )
    (net (code "158") (name "Net-(U1J-TDI)") (class "Default")
      (node (ref "P1") (pin "9") (pinfunction "9_9") (pintype "passive"))
      (node (ref "R6") (pin "1") (pinfunction "1_1") (pintype "passive"))
      (node (ref "U1") (pin "H4") (pinfunction "TDI_H4") (pintype "input"))
    )
    (net (code "159") (name "Net-(U1J-TDO)") (class "Default")
      (node (ref "P1") (pin "3") (pinfunction "3_3") (pintype "passive"))
      (node (ref "R5") (pin "1") (pinfunction "1_1") (pintype "passive"))
      (node (ref "U1") (pin "J4") (pinfunction "TDO_J4") (pintype "output"))
    )
    (net (code "160") (name "Net-(U1J-TMS)") (class "Default")
      (node (ref "P1") (pin "5") (pinfunction "5_5") (pintype "passive"))
      (node (ref "U1") (pin "J5") (pinfunction "TMS_J5") (pintype "input"))
    )
    (net (code "161") (name "Net-(U1J-nSTATUS)") (class "Default")
      (node (ref "R1") (pin "1") (pinfunction "1_1") (pintype "passive"))
      (node (ref "U1") (pin "F4") (pinfunction "nSTATUS_F4") (pintype "bidirectional"))
    )
    (net (code "162") (name "unconnected-(P1-Pad7)") (class "Default")
      (node (ref "P1") (pin "7") (pinfunction "7_7") (pintype "passive"))
    )
    (net (code "163") (name "unconnected-(P1-Pad8)") (class "Default")
      (node (ref "P1") (pin "8") (pinfunction "8_8") (pintype "passive"))
    )
  )
)
